# adhit_RR.net
KiCad netlist of a schematic drawn in EAGLE
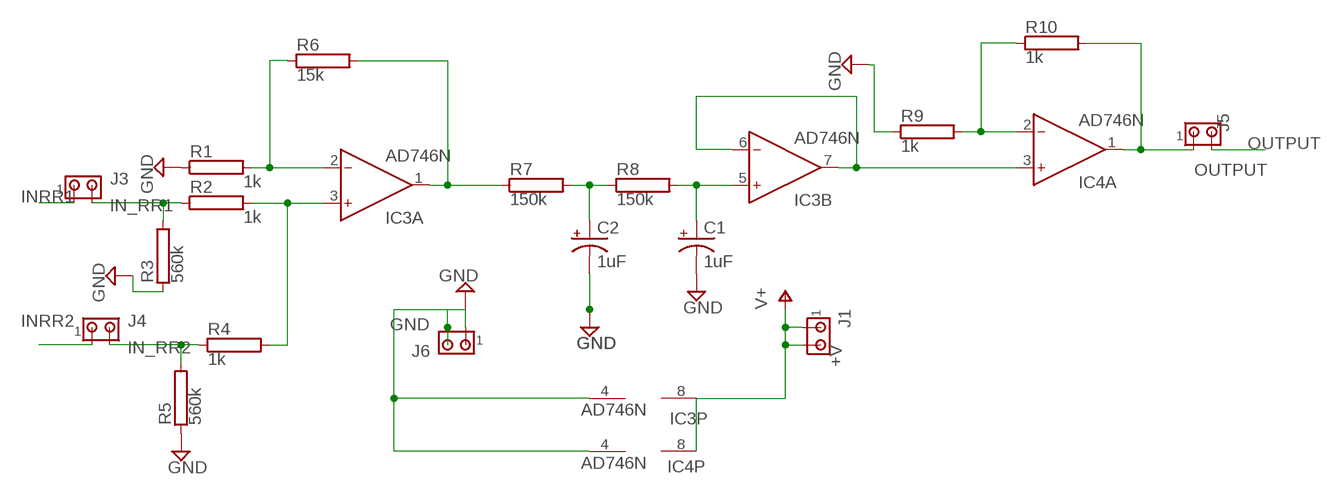
[diagram p0: schematic, sheet 1]

(export (version "E")
  (design (tool "Eeschema 10.0.6"))
  (components
    (comp (ref "C1")
      (value "1uF")
      (footprint "eagle-import:E2,5-6E")
      (libsource (lib "eagle-import") (part "CPOL-USE2,5-6E"))
    )
    (comp (ref "C2")
      (value "1uF")
      (footprint "eagle-import:E2,5-6E")
      (libsource (lib "eagle-import") (part "CPOL-USE2,5-6E"))
    )
    (comp (ref "IC3")
      (value "AD746N")
      (footprint "eagle-import:DIL08")
      (fields (field (name "MF") "ALTERA CORPORATION") (field (name "MPN") "AD746JNZ"))
      (libsource (lib "eagle-import") (part "AD746N"))
    )
    (comp (ref "IC4")
      (value "AD746N")
      (footprint "eagle-import:DIL08")
      (fields (field (name "MF") "ALTERA CORPORATION") (field (name "MPN") "AD746JNZ"))
      (libsource (lib "eagle-import") (part "AD746N"))
    )
    (comp (ref "J1")
      (value "+V")
      (footprint "eagle-import:1X2MTA")
      (libsource (lib "eagle-import") (part "MTA02-156"))
    )
    (comp (ref "J3")
      (value "IN_RR1")
      (footprint "eagle-import:1X2MTA")
      (libsource (lib "eagle-import") (part "MTA02-156"))
    )
    (comp (ref "J4")
      (value "IN_RR2")
      (footprint "eagle-import:1X2MTA")
      (libsource (lib "eagle-import") (part "MTA02-156"))
    )
    (comp (ref "J5")
      (value "OUTPUT")
      (footprint "eagle-import:1X2MTA")
      (libsource (lib "eagle-import") (part "MTA02-156"))
    )
    (comp (ref "J6")
      (value "GND")
      (footprint "eagle-import:1X2MTA")
      (libsource (lib "eagle-import") (part "MTA02-156"))
    )
    (comp (ref "R1")
      (value "1k")
      (footprint "eagle-import:AC01")
      (libsource (lib "eagle-import") (part "RAC01"))
    )
    (comp (ref "R2")
      (value "1k")
      (footprint "eagle-import:AC01")
      (libsource (lib "eagle-import") (part "RAC01"))
    )
    (comp (ref "R3")
      (value "560k")
      (footprint "eagle-import:AC01")
      (libsource (lib "eagle-import") (part "RAC01"))
    )
    (comp (ref "R4")
      (value "1k")
      (footprint "eagle-import:AC01")
      (libsource (lib "eagle-import") (part "RAC01"))
    )
    (comp (ref "R5")
      (value "560k")
      (footprint "eagle-import:AC01")
      (libsource (lib "eagle-import") (part "RAC01"))
    )
    (comp (ref "R6")
      (value "15k")
      (footprint "eagle-import:AC01")
      (libsource (lib "eagle-import") (part "RAC01"))
    )
    (comp (ref "R7")
      (value "150k")
      (footprint "eagle-import:AC01")
      (libsource (lib "eagle-import") (part "RAC01"))
    )
    (comp (ref "R8")
      (value "150k")
      (footprint "eagle-import:AC01")
      (libsource (lib "eagle-import") (part "RAC01"))
    )
    (comp (ref "R9")
      (value "1k")
      (footprint "eagle-import:AC01")
      (libsource (lib "eagle-import") (part "RAC01"))
    )
    (comp (ref "R10")
      (value "1k")
      (footprint "eagle-import:AC01")
      (libsource (lib "eagle-import") (part "RAC01"))
    )
  )
  (nets
    (net (code "1") (name "/INRR1") (class "Default")
      (node (ref "J3") (pin "1") (pinfunction "1_1") (pintype "passive"))
    )
    (net (code "2") (name "/INRR2") (class "Default")
      (node (ref "J4") (pin "1") (pinfunction "1_1") (pintype "passive"))
    )
    (net (code "3") (name "/OUTPUT") (class "Default")
      (node (ref "J5") (pin "2") (pinfunction "2_2") (pintype "passive"))
    )
    (net (code "4") (name "GND") (class "Default")
      (node (ref "C1") (pin "-") (pinfunction "-_-") (pintype "passive"))
      (node (ref "C2") (pin "-") (pinfunction "-_-") (pintype "passive"))
      (node (ref "IC3") (pin "4") (pinfunction "V-_4") (pintype "power_in"))
      (node (ref "IC4") (pin "4") (pinfunction "V-_4") (pintype "power_in"))
      (node (ref "J6") (pin "1") (pinfunction "1_1") (pintype "passive"))
      (node (ref "J6") (pin "2") (pinfunction "2_2") (pintype "passive"))
      (node (ref "R1") (pin "1") (pinfunction "1_1") (pintype "passive"))
      (node (ref "R3") (pin "1") (pinfunction "1_1") (pintype "passive"))
      (node (ref "R5") (pin "1") (pinfunction "1_1") (pintype "passive"))
      (node (ref "R9") (pin "1") (pinfunction "1_1") (pintype "passive"))
    )
    (net (code "5") (name "Net-(C2-Pad+)") (class "Default")
      (node (ref "C2") (pin "+") (pinfunction "+_+") (pintype "passive"))
      (node (ref "R7") (pin "2") (pinfunction "2_2") (pintype "passive"))
      (node (ref "R8") (pin "1") (pinfunction "1_1") (pintype "passive"))
    )
    (net (code "6") (name "Net-(IC3A-IN+)") (class "Default")
      (node (ref "IC3") (pin "3") (pinfunction "IN+_3") (pintype "input"))
      (node (ref "R2") (pin "2") (pinfunction "2_2") (pintype "passive"))
      (node (ref "R4") (pin "2") (pinfunction "2_2") (pintype "passive"))
    )
    (net (code "7") (name "Net-(IC3A-IN-)") (class "Default")
      (node (ref "IC3") (pin "2") (pinfunction "IN-_2") (pintype "input"))
      (node (ref "R1") (pin "2") (pinfunction "2_2") (pintype "passive"))
      (node (ref "R6") (pin "1") (pinfunction "1_1") (pintype "passive"))
    )
    (net (code "8") (name "Net-(IC3A-OUT)") (class "Default")
      (node (ref "IC3") (pin "1") (pinfunction "OUT_1") (pintype "output"))
      (node (ref "R6") (pin "2") (pinfunction "2_2") (pintype "passive"))
      (node (ref "R7") (pin "1") (pinfunction "1_1") (pintype "passive"))
    )
    (net (code "9") (name "Net-(IC3B-IN+)") (class "Default")
      (node (ref "C1") (pin "+") (pinfunction "+_+") (pintype "passive"))
      (node (ref "IC3") (pin "5") (pinfunction "IN+_5") (pintype "input"))
      (node (ref "R8") (pin "2") (pinfunction "2_2") (pintype "passive"))
    )
    (net (code "10") (name "Net-(IC3B-IN-)") (class "Default")
      (node (ref "IC3") (pin "6") (pinfunction "IN-_6") (pintype "input"))
      (node (ref "IC3") (pin "7") (pinfunction "OUT_7") (pintype "output"))
      (node (ref "IC4") (pin "3") (pinfunction "IN+_3") (pintype "input"))
    )
    (net (code "11") (name "Net-(IC4A-IN-)") (class "Default")
      (node (ref "IC4") (pin "2") (pinfunction "IN-_2") (pintype "input"))
      (node (ref "R10") (pin "1") (pinfunction "1_1") (pintype "passive"))
      (node (ref "R9") (pin "2") (pinfunction "2_2") (pintype "passive"))
    )
    (net (code "12") (name "Net-(IC4A-OUT)") (class "Default")
      (node (ref "IC4") (pin "1") (pinfunction "OUT_1") (pintype "output"))
      (node (ref "J5") (pin "1") (pinfunction "1_1") (pintype "passive"))
      (node (ref "R10") (pin "2") (pinfunction "2_2") (pintype "passive"))
    )
    (net (code "13") (name "Net-(J3-Pad2)") (class "Default")
      (node (ref "J3") (pin "2") (pinfunction "2_2") (pintype "passive"))
      (node (ref "R2") (pin "1") (pinfunction "1_1") (pintype "passive"))
      (node (ref "R3") (pin "2") (pinfunction "2_2") (pintype "passive"))
    )
    (net (code "14") (name "Net-(J4-Pad2)") (class "Default")
      (node (ref "J4") (pin "2") (pinfunction "2_2") (pintype "passive"))
      (node (ref "R4") (pin "1") (pinfunction "1_1") (pintype "passive"))
      (node (ref "R5") (pin "2") (pinfunction "2_2") (pintype "passive"))
    )
    (net (code "15") (name "V+") (class "Default")
      (node (ref "IC3") (pin "8") (pinfunction "V+_8") (pintype "power_in"))
      (node (ref "IC4") (pin "8") (pinfunction "V+_8") (pintype "power_in"))
      (node (ref "J1") (pin "1") (pinfunction "1_1") (pintype "passive"))
      (node (ref "J1") (pin "2") (pinfunction "2_2") (pintype "passive"))
    )
  )
)
